# kachisys_board.net
KiCad netlist of a schematic drawn in EAGLE
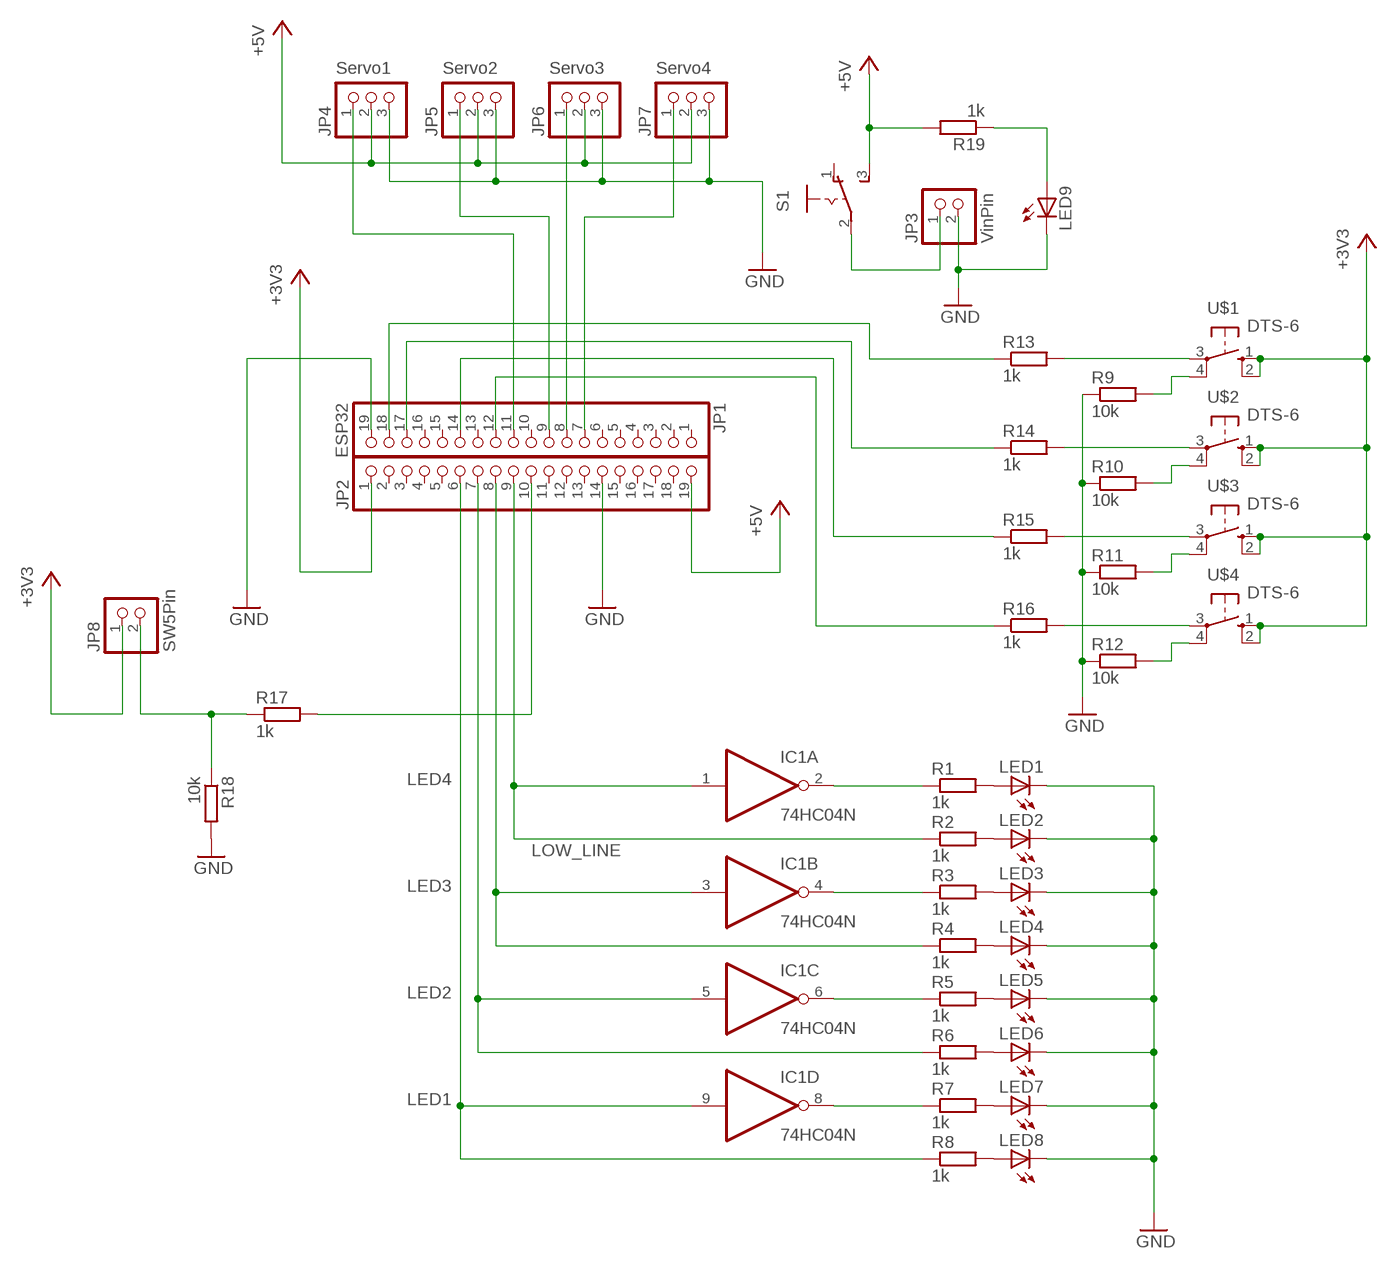
[diagram p0: schematic, sheet 1]

(export (version "E")
  (design (tool "Eeschema 10.0.6"))
  (components
    (comp (ref "IC1")
      (value "74HC04N")
      (footprint "eagle-import:DIL14")
      (libsource (lib "eagle-import") (part "7404NHC"))
    )
    (comp (ref "JP1")
      (value "ESP32")
      (footprint "eagle-import:1X19")
      (libsource (lib "eagle-import") (part "PINHD-1X19"))
    )
    (comp (ref "JP2")
      (value "PINHD-1X19")
      (footprint "eagle-import:1X19")
      (libsource (lib "eagle-import") (part "PINHD-1X19"))
    )
    (comp (ref "JP3")
      (value "VinPin")
      (footprint "eagle-import:1X02_90")
      (libsource (lib "eagle-import") (part "PINHD-1X2/90"))
    )
    (comp (ref "JP4")
      (value "PINHD-1X3")
      (footprint "eagle-import:1X03")
      (libsource (lib "eagle-import") (part "PINHD-1X3"))
    )
    (comp (ref "JP5")
      (value "PINHD-1X3")
      (footprint "eagle-import:1X03")
      (libsource (lib "eagle-import") (part "PINHD-1X3"))
    )
    (comp (ref "JP6")
      (value "PINHD-1X3")
      (footprint "eagle-import:1X03")
      (libsource (lib "eagle-import") (part "PINHD-1X3"))
    )
    (comp (ref "JP7")
      (value "PINHD-1X3")
      (footprint "eagle-import:1X03")
      (libsource (lib "eagle-import") (part "PINHD-1X3"))
    )
    (comp (ref "JP8")
      (value "SW5Pin")
      (footprint "eagle-import:1X02_90")
      (libsource (lib "eagle-import") (part "PINHD-1X2/90"))
    )
    (comp (ref "LED1")
      (value "LED3MM")
      (footprint "eagle-import:LED3MM")
      (libsource (lib "eagle-import") (part "LED3MM"))
    )
    (comp (ref "LED2")
      (value "LED3MM")
      (footprint "eagle-import:LED3MM")
      (libsource (lib "eagle-import") (part "LED3MM"))
    )
    (comp (ref "LED3")
      (value "LED3MM")
      (footprint "eagle-import:LED3MM")
      (libsource (lib "eagle-import") (part "LED3MM"))
    )
    (comp (ref "LED4")
      (value "LED3MM")
      (footprint "eagle-import:LED3MM")
      (libsource (lib "eagle-import") (part "LED3MM"))
    )
    (comp (ref "LED5")
      (value "LED3MM")
      (footprint "eagle-import:LED3MM")
      (libsource (lib "eagle-import") (part "LED3MM"))
    )
    (comp (ref "LED6")
      (value "LED3MM")
      (footprint "eagle-import:LED3MM")
      (libsource (lib "eagle-import") (part "LED3MM"))
    )
    (comp (ref "LED7")
      (value "LED3MM")
      (footprint "eagle-import:LED3MM")
      (libsource (lib "eagle-import") (part "LED3MM"))
    )
    (comp (ref "LED8")
      (value "LED3MM")
      (footprint "eagle-import:LED3MM")
      (libsource (lib "eagle-import") (part "LED3MM"))
    )
    (comp (ref "LED9")
      (value "LED3MM")
      (footprint "eagle-import:LED3MM")
      (libsource (lib "eagle-import") (part "LED3MM"))
    )
    (comp (ref "R1")
      (value "1k")
      (footprint "eagle-import:M2012")
      (libsource (lib "eagle-import") (part "R-EU_M2012"))
    )
    (comp (ref "R2")
      (value "1k")
      (footprint "eagle-import:M2012")
      (libsource (lib "eagle-import") (part "R-EU_M2012"))
    )
    (comp (ref "R3")
      (value "1k")
      (footprint "eagle-import:M2012")
      (libsource (lib "eagle-import") (part "R-EU_M2012"))
    )
    (comp (ref "R4")
      (value "1k")
      (footprint "eagle-import:M2012")
      (libsource (lib "eagle-import") (part "R-EU_M2012"))
    )
    (comp (ref "R5")
      (value "1k")
      (footprint "eagle-import:M2012")
      (libsource (lib "eagle-import") (part "R-EU_M2012"))
    )
    (comp (ref "R6")
      (value "1k")
      (footprint "eagle-import:M2012")
      (libsource (lib "eagle-import") (part "R-EU_M2012"))
    )
    (comp (ref "R7")
      (value "1k")
      (footprint "eagle-import:M2012")
      (libsource (lib "eagle-import") (part "R-EU_M2012"))
    )
    (comp (ref "R8")
      (value "1k")
      (footprint "eagle-import:M2012")
      (libsource (lib "eagle-import") (part "R-EU_M2012"))
    )
    (comp (ref "R9")
      (value "10k")
      (footprint "eagle-import:M2012")
      (libsource (lib "eagle-import") (part "R-EU_M2012"))
    )
    (comp (ref "R10")
      (value "10k")
      (footprint "eagle-import:M2012")
      (libsource (lib "eagle-import") (part "R-EU_M2012"))
    )
    (comp (ref "R11")
      (value "10k")
      (footprint "eagle-import:M2012")
      (libsource (lib "eagle-import") (part "R-EU_M2012"))
    )
    (comp (ref "R12")
      (value "10k")
      (footprint "eagle-import:M2012")
      (libsource (lib "eagle-import") (part "R-EU_M2012"))
    )
    (comp (ref "R13")
      (value "1k")
      (footprint "eagle-import:M2012")
      (libsource (lib "eagle-import") (part "R-EU_M2012"))
    )
    (comp (ref "R14")
      (value "1k")
      (footprint "eagle-import:M2012")
      (libsource (lib "eagle-import") (part "R-EU_M2012"))
    )
    (comp (ref "R15")
      (value "1k")
      (footprint "eagle-import:M2012")
      (libsource (lib "eagle-import") (part "R-EU_M2012"))
    )
    (comp (ref "R16")
      (value "1k")
      (footprint "eagle-import:M2012")
      (libsource (lib "eagle-import") (part "R-EU_M2012"))
    )
    (comp (ref "R17")
      (value "1k")
      (footprint "eagle-import:M2012")
      (libsource (lib "eagle-import") (part "R-EU_M2012"))
    )
    (comp (ref "R18")
      (value "10k")
      (footprint "eagle-import:M2012")
      (libsource (lib "eagle-import") (part "R-EU_M2012"))
    )
    (comp (ref "R19")
      (value "1k")
      (footprint "eagle-import:M2012")
      (libsource (lib "eagle-import") (part "R-EU_M2012"))
    )
    (comp (ref "S1")
      (value "255SB")
      (footprint "eagle-import:255SB")
      (libsource (lib "eagle-import") (part "255SB"))
    )
    (comp (ref "U$1")
      (value "DTS-6")
      (footprint "eagle-import:DTS6")
      (libsource (lib "eagle-import") (part "DTS-6"))
    )
    (comp (ref "U$2")
      (value "DTS-6")
      (footprint "eagle-import:DTS6")
      (libsource (lib "eagle-import") (part "DTS-6"))
    )
    (comp (ref "U$3")
      (value "DTS-6")
      (footprint "eagle-import:DTS6")
      (libsource (lib "eagle-import") (part "DTS-6"))
    )
    (comp (ref "U$4")
      (value "DTS-6")
      (footprint "eagle-import:DTS6")
      (libsource (lib "eagle-import") (part "DTS-6"))
    )
  )
  (nets
    (net (code "1") (name "+3V3") (class "Default")
      (node (ref "JP2") (pin "1") (pinfunction "1_1") (pintype "passive"))
      (node (ref "JP8") (pin "1") (pinfunction "1_1") (pintype "passive"))
      (node (ref "U$1") (pin "1") (pinfunction "S_1") (pintype "passive"))
      (node (ref "U$1") (pin "2") (pinfunction "S1_2") (pintype "passive"))
      (node (ref "U$2") (pin "1") (pinfunction "S_1") (pintype "passive"))
      (node (ref "U$2") (pin "2") (pinfunction "S1_2") (pintype "passive"))
      (node (ref "U$3") (pin "1") (pinfunction "S_1") (pintype "passive"))
      (node (ref "U$3") (pin "2") (pinfunction "S1_2") (pintype "passive"))
      (node (ref "U$4") (pin "1") (pinfunction "S_1") (pintype "passive"))
      (node (ref "U$4") (pin "2") (pinfunction "S1_2") (pintype "passive"))
    )
    (net (code "2") (name "+5V") (class "Default")
      (node (ref "JP2") (pin "19") (pinfunction "19_19") (pintype "passive"))
      (node (ref "JP4") (pin "2") (pinfunction "2_2") (pintype "passive"))
      (node (ref "JP5") (pin "2") (pinfunction "2_2") (pintype "passive"))
      (node (ref "JP6") (pin "2") (pinfunction "2_2") (pintype "passive"))
      (node (ref "JP7") (pin "2") (pinfunction "2_2") (pintype "passive"))
      (node (ref "R19") (pin "2") (pinfunction "2_2") (pintype "passive"))
      (node (ref "S1") (pin "3") (pinfunction "S_3") (pintype "passive"))
    )
    (net (code "3") (name "GND") (class "Default")
      (node (ref "JP1") (pin "19") (pinfunction "19_19") (pintype "passive"))
      (node (ref "JP2") (pin "14") (pinfunction "14_14") (pintype "passive"))
      (node (ref "JP3") (pin "2") (pinfunction "2_2") (pintype "passive"))
      (node (ref "JP4") (pin "3") (pinfunction "3_3") (pintype "passive"))
      (node (ref "JP5") (pin "3") (pinfunction "3_3") (pintype "passive"))
      (node (ref "JP6") (pin "3") (pinfunction "3_3") (pintype "passive"))
      (node (ref "JP7") (pin "3") (pinfunction "3_3") (pintype "passive"))
      (node (ref "LED1") (pin "K") (pinfunction "C_K") (pintype "passive"))
      (node (ref "LED2") (pin "K") (pinfunction "C_K") (pintype "passive"))
      (node (ref "LED3") (pin "K") (pinfunction "C_K") (pintype "passive"))
      (node (ref "LED4") (pin "K") (pinfunction "C_K") (pintype "passive"))
      (node (ref "LED5") (pin "K") (pinfunction "C_K") (pintype "passive"))
      (node (ref "LED6") (pin "K") (pinfunction "C_K") (pintype "passive"))
      (node (ref "LED7") (pin "K") (pinfunction "C_K") (pintype "passive"))
      (node (ref "LED8") (pin "K") (pinfunction "C_K") (pintype "passive"))
      (node (ref "LED9") (pin "K") (pinfunction "C_K") (pintype "passive"))
      (node (ref "R10") (pin "1") (pinfunction "1_1") (pintype "passive"))
      (node (ref "R11") (pin "1") (pinfunction "1_1") (pintype "passive"))
      (node (ref "R12") (pin "1") (pinfunction "1_1") (pintype "passive"))
      (node (ref "R18") (pin "2") (pinfunction "2_2") (pintype "passive"))
      (node (ref "R9") (pin "1") (pinfunction "1_1") (pintype "passive"))
    )
    (net (code "4") (name "Net-(IC1A-I)") (class "Default")
      (node (ref "IC1") (pin "1") (pinfunction "I_1") (pintype "input"))
      (node (ref "JP2") (pin "9") (pinfunction "9_9") (pintype "passive"))
      (node (ref "R2") (pin "1") (pinfunction "1_1") (pintype "passive"))
    )
    (net (code "5") (name "Net-(IC1A-O)") (class "Default")
      (node (ref "IC1") (pin "2") (pinfunction "O_2") (pintype "output"))
      (node (ref "R1") (pin "1") (pinfunction "1_1") (pintype "passive"))
    )
    (net (code "6") (name "Net-(IC1B-I)") (class "Default")
      (node (ref "IC1") (pin "3") (pinfunction "I_3") (pintype "input"))
      (node (ref "JP2") (pin "8") (pinfunction "8_8") (pintype "passive"))
      (node (ref "R4") (pin "1") (pinfunction "1_1") (pintype "passive"))
    )
    (net (code "7") (name "Net-(IC1B-O)") (class "Default")
      (node (ref "IC1") (pin "4") (pinfunction "O_4") (pintype "output"))
      (node (ref "R3") (pin "1") (pinfunction "1_1") (pintype "passive"))
    )
    (net (code "8") (name "Net-(IC1C-I)") (class "Default")
      (node (ref "IC1") (pin "5") (pinfunction "I_5") (pintype "input"))
      (node (ref "JP2") (pin "7") (pinfunction "7_7") (pintype "passive"))
      (node (ref "R6") (pin "1") (pinfunction "1_1") (pintype "passive"))
    )
    (net (code "9") (name "Net-(IC1C-O)") (class "Default")
      (node (ref "IC1") (pin "6") (pinfunction "O_6") (pintype "output"))
      (node (ref "R5") (pin "1") (pinfunction "1_1") (pintype "passive"))
    )
    (net (code "10") (name "Net-(IC1D-I)") (class "Default")
      (node (ref "IC1") (pin "9") (pinfunction "I_9") (pintype "input"))
      (node (ref "JP2") (pin "6") (pinfunction "6_6") (pintype "passive"))
      (node (ref "R8") (pin "1") (pinfunction "1_1") (pintype "passive"))
    )
    (net (code "11") (name "Net-(IC1D-O)") (class "Default")
      (node (ref "IC1") (pin "8") (pinfunction "O_8") (pintype "output"))
      (node (ref "R7") (pin "1") (pinfunction "1_1") (pintype "passive"))
    )
    (net (code "12") (name "Net-(JP1-Pad7)") (class "Default")
      (node (ref "JP1") (pin "7") (pinfunction "7_7") (pintype "passive"))
      (node (ref "JP7") (pin "1") (pinfunction "1_1") (pintype "passive"))
    )
    (net (code "13") (name "Net-(JP1-Pad8)") (class "Default")
      (node (ref "JP1") (pin "8") (pinfunction "8_8") (pintype "passive"))
      (node (ref "JP6") (pin "1") (pinfunction "1_1") (pintype "passive"))
    )
    (net (code "14") (name "Net-(JP1-Pad9)") (class "Default")
      (node (ref "JP1") (pin "9") (pinfunction "9_9") (pintype "passive"))
      (node (ref "JP5") (pin "1") (pinfunction "1_1") (pintype "passive"))
    )
    (net (code "15") (name "Net-(JP1-Pad11)") (class "Default")
      (node (ref "JP1") (pin "11") (pinfunction "11_11") (pintype "passive"))
      (node (ref "JP4") (pin "1") (pinfunction "1_1") (pintype "passive"))
    )
    (net (code "16") (name "Net-(JP1-Pad12)") (class "Default")
      (node (ref "JP1") (pin "12") (pinfunction "12_12") (pintype "passive"))
      (node (ref "R16") (pin "1") (pinfunction "1_1") (pintype "passive"))
    )
    (net (code "17") (name "Net-(JP1-Pad14)") (class "Default")
      (node (ref "JP1") (pin "14") (pinfunction "14_14") (pintype "passive"))
      (node (ref "R15") (pin "1") (pinfunction "1_1") (pintype "passive"))
    )
    (net (code "18") (name "Net-(JP1-Pad17)") (class "Default")
      (node (ref "JP1") (pin "17") (pinfunction "17_17") (pintype "passive"))
      (node (ref "R14") (pin "1") (pinfunction "1_1") (pintype "passive"))
    )
    (net (code "19") (name "Net-(JP1-Pad18)") (class "Default")
      (node (ref "JP1") (pin "18") (pinfunction "18_18") (pintype "passive"))
      (node (ref "R13") (pin "1") (pinfunction "1_1") (pintype "passive"))
    )
    (net (code "20") (name "Net-(JP2-Pad10)") (class "Default")
      (node (ref "JP2") (pin "10") (pinfunction "10_10") (pintype "passive"))
      (node (ref "R17") (pin "2") (pinfunction "2_2") (pintype "passive"))
    )
    (net (code "21") (name "Net-(JP8-Pad2)") (class "Default")
      (node (ref "JP8") (pin "2") (pinfunction "2_2") (pintype "passive"))
      (node (ref "R17") (pin "1") (pinfunction "1_1") (pintype "passive"))
      (node (ref "R18") (pin "1") (pinfunction "1_1") (pintype "passive"))
    )
    (net (code "22") (name "Net-(LED1-PadA)") (class "Default")
      (node (ref "LED1") (pin "A") (pinfunction "A_A") (pintype "passive"))
      (node (ref "R1") (pin "2") (pinfunction "2_2") (pintype "passive"))
    )
    (net (code "23") (name "Net-(LED2-PadA)") (class "Default")
      (node (ref "LED2") (pin "A") (pinfunction "A_A") (pintype "passive"))
      (node (ref "R2") (pin "2") (pinfunction "2_2") (pintype "passive"))
    )
    (net (code "24") (name "Net-(LED3-PadA)") (class "Default")
      (node (ref "LED3") (pin "A") (pinfunction "A_A") (pintype "passive"))
      (node (ref "R3") (pin "2") (pinfunction "2_2") (pintype "passive"))
    )
    (net (code "25") (name "Net-(LED4-PadA)") (class "Default")
      (node (ref "LED4") (pin "A") (pinfunction "A_A") (pintype "passive"))
      (node (ref "R4") (pin "2") (pinfunction "2_2") (pintype "passive"))
    )
    (net (code "26") (name "Net-(LED5-PadA)") (class "Default")
      (node (ref "LED5") (pin "A") (pinfunction "A_A") (pintype "passive"))
      (node (ref "R5") (pin "2") (pinfunction "2_2") (pintype "passive"))
    )
    (net (code "27") (name "Net-(LED6-PadA)") (class "Default")
      (node (ref "LED6") (pin "A") (pinfunction "A_A") (pintype "passive"))
      (node (ref "R6") (pin "2") (pinfunction "2_2") (pintype "passive"))
    )
    (net (code "28") (name "Net-(LED7-PadA)") (class "Default")
      (node (ref "LED7") (pin "A") (pinfunction "A_A") (pintype "passive"))
      (node (ref "R7") (pin "2") (pinfunction "2_2") (pintype "passive"))
    )
    (net (code "29") (name "Net-(LED8-PadA)") (class "Default")
      (node (ref "LED8") (pin "A") (pinfunction "A_A") (pintype "passive"))
      (node (ref "R8") (pin "2") (pinfunction "2_2") (pintype "passive"))
    )
    (net (code "30") (name "Net-(LED9-PadA)") (class "Default")
      (node (ref "LED9") (pin "A") (pinfunction "A_A") (pintype "passive"))
      (node (ref "R19") (pin "1") (pinfunction "1_1") (pintype "passive"))
    )
    (net (code "31") (name "Net-(S1-P)") (class "Default")
      (node (ref "JP3") (pin "1") (pinfunction "1_1") (pintype "passive"))
      (node (ref "S1") (pin "2") (pinfunction "P_2") (pintype "passive"))
    )
    (net (code "32") (name "Net-(U$1-P)") (class "Default")
      (node (ref "R13") (pin "2") (pinfunction "2_2") (pintype "passive"))
      (node (ref "U$1") (pin "3") (pinfunction "P_3") (pintype "passive"))
    )
    (net (code "33") (name "Net-(U$1-P1)") (class "Default")
      (node (ref "R9") (pin "2") (pinfunction "2_2") (pintype "passive"))
      (node (ref "U$1") (pin "4") (pinfunction "P1_4") (pintype "passive"))
    )
    (net (code "34") (name "Net-(U$2-P)") (class "Default")
      (node (ref "R14") (pin "2") (pinfunction "2_2") (pintype "passive"))
      (node (ref "U$2") (pin "3") (pinfunction "P_3") (pintype "passive"))
    )
    (net (code "35") (name "Net-(U$2-P1)") (class "Default")
      (node (ref "R10") (pin "2") (pinfunction "2_2") (pintype "passive"))
      (node (ref "U$2") (pin "4") (pinfunction "P1_4") (pintype "passive"))
    )
    (net (code "36") (name "Net-(U$3-P)") (class "Default")
      (node (ref "R15") (pin "2") (pinfunction "2_2") (pintype "passive"))
      (node (ref "U$3") (pin "3") (pinfunction "P_3") (pintype "passive"))
    )
    (net (code "37") (name "Net-(U$3-P1)") (class "Default")
      (node (ref "R11") (pin "2") (pinfunction "2_2") (pintype "passive"))
      (node (ref "U$3") (pin "4") (pinfunction "P1_4") (pintype "passive"))
    )
    (net (code "38") (name "Net-(U$4-P)") (class "Default")
      (node (ref "R16") (pin "2") (pinfunction "2_2") (pintype "passive"))
      (node (ref "U$4") (pin "3") (pinfunction "P_3") (pintype "passive"))
    )
    (net (code "39") (name "Net-(U$4-P1)") (class "Default")
      (node (ref "R12") (pin "2") (pinfunction "2_2") (pintype "passive"))
      (node (ref "U$4") (pin "4") (pinfunction "P1_4") (pintype "passive"))
    )
    (net (code "40") (name "unconnected-(JP1-Pad1)") (class "Default")
      (node (ref "JP1") (pin "1") (pinfunction "1_1") (pintype "passive"))
    )
    (net (code "41") (name "unconnected-(JP1-Pad2)") (class "Default")
      (node (ref "JP1") (pin "2") (pinfunction "2_2") (pintype "passive"))
    )
    (net (code "42") (name "unconnected-(JP1-Pad3)") (class "Default")
      (node (ref "JP1") (pin "3") (pinfunction "3_3") (pintype "passive"))
    )
    (net (code "43") (name "unconnected-(JP1-Pad4)") (class "Default")
      (node (ref "JP1") (pin "4") (pinfunction "4_4") (pintype "passive"))
    )
    (net (code "44") (name "unconnected-(JP1-Pad5)") (class "Default")
      (node (ref "JP1") (pin "5") (pinfunction "5_5") (pintype "passive"))
    )
    (net (code "45") (name "unconnected-(JP1-Pad6)") (class "Default")
      (node (ref "JP1") (pin "6") (pinfunction "6_6") (pintype "passive"))
    )
    (net (code "46") (name "unconnected-(JP1-Pad10)") (class "Default")
      (node (ref "JP1") (pin "10") (pinfunction "10_10") (pintype "passive"))
    )
    (net (code "47") (name "unconnected-(JP1-Pad13)") (class "Default")
      (node (ref "JP1") (pin "13") (pinfunction "13_13") (pintype "passive"))
    )
    (net (code "48") (name "unconnected-(JP1-Pad15)") (class "Default")
      (node (ref "JP1") (pin "15") (pinfunction "15_15") (pintype "passive"))
    )
    (net (code "49") (name "unconnected-(JP1-Pad16)") (class "Default")
      (node (ref "JP1") (pin "16") (pinfunction "16_16") (pintype "passive"))
    )
    (net (code "50") (name "unconnected-(JP2-Pad2)") (class "Default")
      (node (ref "JP2") (pin "2") (pinfunction "2_2") (pintype "passive"))
    )
    (net (code "51") (name "unconnected-(JP2-Pad3)") (class "Default")
      (node (ref "JP2") (pin "3") (pinfunction "3_3") (pintype "passive"))
    )
    (net (code "52") (name "unconnected-(JP2-Pad4)") (class "Default")
      (node (ref "JP2") (pin "4") (pinfunction "4_4") (pintype "passive"))
    )
    (net (code "53") (name "unconnected-(JP2-Pad5)") (class "Default")
      (node (ref "JP2") (pin "5") (pinfunction "5_5") (pintype "passive"))
    )
    (net (code "54") (name "unconnected-(JP2-Pad11)") (class "Default")
      (node (ref "JP2") (pin "11") (pinfunction "11_11") (pintype "passive"))
    )
    (net (code "55") (name "unconnected-(JP2-Pad12)") (class "Default")
      (node (ref "JP2") (pin "12") (pinfunction "12_12") (pintype "passive"))
    )
    (net (code "56") (name "unconnected-(JP2-Pad13)") (class "Default")
      (node (ref "JP2") (pin "13") (pinfunction "13_13") (pintype "passive"))
    )
    (net (code "57") (name "unconnected-(JP2-Pad15)") (class "Default")
      (node (ref "JP2") (pin "15") (pinfunction "15_15") (pintype "passive"))
    )
    (net (code "58") (name "unconnected-(JP2-Pad16)") (class "Default")
      (node (ref "JP2") (pin "16") (pinfunction "16_16") (pintype "passive"))
    )
    (net (code "59") (name "unconnected-(JP2-Pad17)") (class "Default")
      (node (ref "JP2") (pin "17") (pinfunction "17_17") (pintype "passive"))
    )
    (net (code "60") (name "unconnected-(JP2-Pad18)") (class "Default")
      (node (ref "JP2") (pin "18") (pinfunction "18_18") (pintype "passive"))
    )
    (net (code "61") (name "unconnected-(S1-O-Pad1)") (class "Default")
      (node (ref "S1") (pin "1") (pinfunction "O_1") (pintype "passive"))
    )
  )
)
